# MaleHeader.net
KiCad netlist of a schematic drawn in Altium Designer
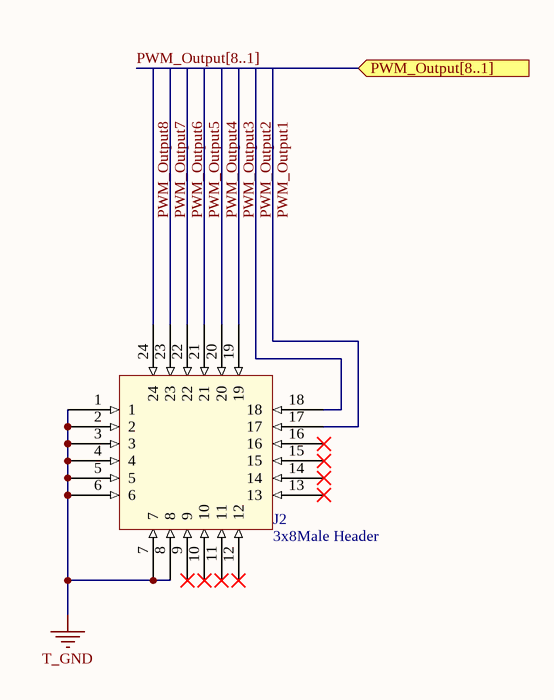
[diagram p0: MaleHeader.SchDoc]

(export (version "E")
  (design (tool "Eeschema 10.0.6"))
  (components
    (comp (ref "J2")
      (value "3x8Male Header")
      (footprint "3x8 Male Header")
      (description "3x8 male header")
      (fields (field (name "MANUFACTURER") "URC") (field (name "MANUFACTURER PART NUMBER") "Custom"))
      (libsource (lib "3x8 Male Header") (part "3x8Male Header"))
    )
  )
  (nets
    (net (code "1") (name "/PWM_Output1") (class "Default")
      (node (ref "J2") (pin "17") (pinfunction "17_17") (pintype "input"))
    )
    (net (code "2") (name "/PWM_Output2") (class "Default")
      (node (ref "J2") (pin "18") (pinfunction "18_18") (pintype "input"))
    )
    (net (code "3") (name "/PWM_Output3") (class "Default")
      (node (ref "J2") (pin "19") (pinfunction "19_19") (pintype "input"))
    )
    (net (code "4") (name "/PWM_Output4") (class "Default")
      (node (ref "J2") (pin "20") (pinfunction "20_20") (pintype "input"))
    )
    (net (code "5") (name "/PWM_Output5") (class "Default")
      (node (ref "J2") (pin "21") (pinfunction "21_21") (pintype "input"))
    )
    (net (code "6") (name "/PWM_Output6") (class "Default")
      (node (ref "J2") (pin "22") (pinfunction "22_22") (pintype "input"))
    )
    (net (code "7") (name "/PWM_Output7") (class "Default")
      (node (ref "J2") (pin "23") (pinfunction "23_23") (pintype "input"))
    )
    (net (code "8") (name "/PWM_Output8") (class "Default")
      (node (ref "J2") (pin "24") (pinfunction "24_24") (pintype "input"))
    )
    (net (code "10") (name "T_GND") (class "Default")
      (node (ref "J2") (pin "1") (pinfunction "1_1") (pintype "input"))
      (node (ref "J2") (pin "2") (pinfunction "2_2") (pintype "input"))
      (node (ref "J2") (pin "3") (pinfunction "3_3") (pintype "input"))
      (node (ref "J2") (pin "4") (pinfunction "4_4") (pintype "input"))
      (node (ref "J2") (pin "5") (pinfunction "5_5") (pintype "input"))
      (node (ref "J2") (pin "6") (pinfunction "6_6") (pintype "input"))
      (node (ref "J2") (pin "7") (pinfunction "7_7") (pintype "input"))
      (node (ref "J2") (pin "8") (pinfunction "8_8") (pintype "input"))
    )
    (net (code "11") (name "unconnected-(J2-Pad9)") (class "Default")
      (node (ref "J2") (pin "9") (pinfunction "9_9") (pintype "input+no_connect"))
    )
    (net (code "12") (name "unconnected-(J2-Pad10)") (class "Default")
      (node (ref "J2") (pin "10") (pinfunction "10_10") (pintype "input+no_connect"))
    )
    (net (code "13") (name "unconnected-(J2-Pad11)") (class "Default")
      (node (ref "J2") (pin "11") (pinfunction "11_11") (pintype "input+no_connect"))
    )
    (net (code "14") (name "unconnected-(J2-Pad12)") (class "Default")
      (node (ref "J2") (pin "12") (pinfunction "12_12") (pintype "input+no_connect"))
    )
    (net (code "15") (name "unconnected-(J2-Pad13)") (class "Default")
      (node (ref "J2") (pin "13") (pinfunction "13_13") (pintype "input+no_connect"))
    )
    (net (code "16") (name "unconnected-(J2-Pad14)") (class "Default")
      (node (ref "J2") (pin "14") (pinfunction "14_14") (pintype "input+no_connect"))
    )
    (net (code "17") (name "unconnected-(J2-Pad15)") (class "Default")
      (node (ref "J2") (pin "15") (pinfunction "15_15") (pintype "input+no_connect"))
    )
    (net (code "18") (name "unconnected-(J2-Pad16)") (class "Default")
      (node (ref "J2") (pin "16") (pinfunction "16_16") (pintype "input+no_connect"))
    )
  )
)
